# Initial_Schematic.net
KiCad netlist of a schematic drawn in EAGLE
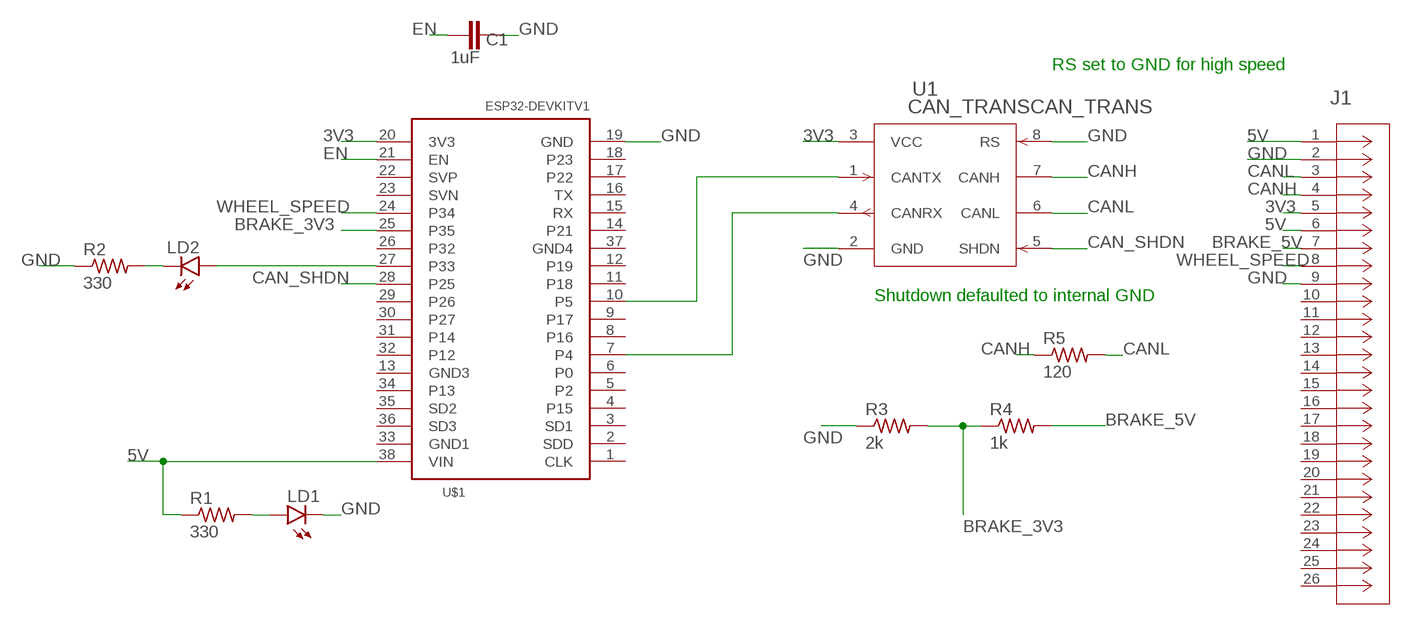
[diagram p0: schematic, sheet 1]

(export (version "E")
  (design (tool "Eeschema 10.0.6"))
  (components
    (comp (ref "C1")
      (value "1uF")
      (footprint "eagle-import:C1206")
      (libsource (lib "eagle-import") (part "CAPACITORC1206"))
    )
    (comp (ref "J1")
      (value "CONNECTOR")
      (footprint "eagle-import:CONN26_9-6437287-8_TEC")
      (fields
        (field (name "MANUFACTURER_PART_NUMBER") "9-6437287-8")
        (field (name "COPYRIGHT") "Copyright (C) 2022 Ultra Librarian. All rights reserved.")
      )
      (libsource (lib "eagle-import") (part "CONNECTOR"))
    )
    (comp (ref "LD1")
      (value "PL006-WCR21")
      (footprint "eagle-import:SOT23")
      (libsource (lib "eagle-import") (part "PL006-WCR21"))
    )
    (comp (ref "LD2")
      (value "PL006-WCR21")
      (footprint "eagle-import:SOT23")
      (libsource (lib "eagle-import") (part "PL006-WCR21"))
    )
    (comp (ref "R1")
      (value "330")
      (footprint "eagle-import:R1206")
      (libsource (lib "eagle-import") (part "RESISTORR1206"))
    )
    (comp (ref "R2")
      (value "330")
      (footprint "eagle-import:R1206")
      (libsource (lib "eagle-import") (part "RESISTORR1206"))
    )
    (comp (ref "R3")
      (value "2k")
      (footprint "eagle-import:R1206")
      (libsource (lib "eagle-import") (part "RESISTORR1206"))
    )
    (comp (ref "R4")
      (value "1k")
      (footprint "eagle-import:R1206")
      (libsource (lib "eagle-import") (part "RESISTORR1206"))
    )
    (comp (ref "R5")
      (value "120")
      (footprint "eagle-import:R1206")
      (libsource (lib "eagle-import") (part "RESISTORR1206"))
    )
    (comp (ref "U$1")
      (value "ESP32DEVKITV1")
      (footprint "eagle-import:ESP32-DEVKITV1")
      (libsource (lib "eagle-import") (part "ESP32DEVKITV1"))
    )
    (comp (ref "U1")
      (value "CAN_TRANSCAN_TRANS")
      (footprint "eagle-import:MAX3051ESA+")
      (fields
        (field (name "MANUFACTURER_PART_NUMBER") "MAX3051ESA+")
        (field (name "COPYRIGHT") "Copyright (C) 2022 Ultra Librarian. All rights reserved.")
      )
      (libsource (lib "eagle-import") (part "CAN_TRANSCAN_TRANS"))
    )
  )
  (nets
    (net (code "1") (name "/3V3") (class "Default")
      (node (ref "J1") (pin "5") (pinfunction "5_5") (pintype "passive"))
      (node (ref "U$1") (pin "20") (pinfunction "3V3_20") (pintype "bidirectional"))
      (node (ref "U1") (pin "3") (pinfunction "VCC_3") (pintype "power_in"))
    )
    (net (code "2") (name "/5V") (class "Default")
      (node (ref "J1") (pin "1") (pinfunction "1_1") (pintype "passive"))
      (node (ref "J1") (pin "6") (pinfunction "6_6") (pintype "passive"))
      (node (ref "R1") (pin "1") (pinfunction "1_1") (pintype "passive"))
      (node (ref "U$1") (pin "38") (pinfunction "VIN_38") (pintype "bidirectional"))
    )
    (net (code "3") (name "/BRAKE_3V3") (class "Default")
      (node (ref "R3") (pin "2") (pinfunction "2_2") (pintype "passive"))
      (node (ref "R4") (pin "1") (pinfunction "1_1") (pintype "passive"))
      (node (ref "U$1") (pin "25") (pinfunction "P35_25") (pintype "bidirectional"))
    )
    (net (code "4") (name "/BRAKE_5V") (class "Default")
      (node (ref "J1") (pin "7") (pinfunction "7_7") (pintype "passive"))
      (node (ref "R4") (pin "2") (pinfunction "2_2") (pintype "passive"))
    )
    (net (code "5") (name "/CANH") (class "Default")
      (node (ref "J1") (pin "4") (pinfunction "4_4") (pintype "passive"))
      (node (ref "R5") (pin "1") (pinfunction "1_1") (pintype "passive"))
      (node (ref "U1") (pin "7") (pinfunction "CANH_7") (pintype "passive"))
    )
    (net (code "6") (name "/CANL") (class "Default")
      (node (ref "J1") (pin "3") (pinfunction "3_3") (pintype "passive"))
      (node (ref "R5") (pin "2") (pinfunction "2_2") (pintype "passive"))
      (node (ref "U1") (pin "6") (pinfunction "CANL_6") (pintype "passive"))
    )
    (net (code "7") (name "/CAN_SHDN") (class "Default")
      (node (ref "U$1") (pin "28") (pinfunction "P25_28") (pintype "bidirectional"))
      (node (ref "U1") (pin "5") (pinfunction "SHDN_5") (pintype "input"))
    )
    (net (code "8") (name "/EN") (class "Default")
      (node (ref "C1") (pin "2") (pinfunction "2_2") (pintype "passive"))
      (node (ref "U$1") (pin "21") (pinfunction "EN_21") (pintype "bidirectional"))
    )
    (net (code "9") (name "/GND") (class "Default")
      (node (ref "C1") (pin "1") (pinfunction "1_1") (pintype "passive"))
      (node (ref "J1") (pin "2") (pinfunction "2_2") (pintype "passive"))
      (node (ref "J1") (pin "9") (pinfunction "9_9") (pintype "passive"))
      (node (ref "LD1") (pin "1") (pinfunction "C_1") (pintype "passive"))
      (node (ref "R2") (pin "1") (pinfunction "1_1") (pintype "passive"))
      (node (ref "R3") (pin "1") (pinfunction "1_1") (pintype "passive"))
      (node (ref "U$1") (pin "19") (pinfunction "GND_19") (pintype "bidirectional"))
      (node (ref "U1") (pin "2") (pinfunction "GND_2") (pintype "power_in"))
      (node (ref "U1") (pin "8") (pinfunction "RS_8") (pintype "input"))
    )
    (net (code "10") (name "/WHEEL_SPEED") (class "Default")
      (node (ref "J1") (pin "8") (pinfunction "8_8") (pintype "passive"))
      (node (ref "U$1") (pin "24") (pinfunction "P34_24") (pintype "bidirectional"))
    )
    (net (code "11") (name "Net-(LD1-A)") (class "Default")
      (node (ref "LD1") (pin "3") (pinfunction "A_3") (pintype "passive"))
      (node (ref "R1") (pin "2") (pinfunction "2_2") (pintype "passive"))
    )
    (net (code "12") (name "Net-(LD2-A)") (class "Default")
      (node (ref "LD2") (pin "3") (pinfunction "A_3") (pintype "passive"))
      (node (ref "U$1") (pin "27") (pinfunction "P33_27") (pintype "bidirectional"))
    )
    (net (code "13") (name "Net-(LD2-C)") (class "Default")
      (node (ref "LD2") (pin "1") (pinfunction "C_1") (pintype "passive"))
      (node (ref "R2") (pin "2") (pinfunction "2_2") (pintype "passive"))
    )
    (net (code "14") (name "Net-(U$1-P4)") (class "Default")
      (node (ref "U$1") (pin "7") (pinfunction "P4_7") (pintype "bidirectional"))
      (node (ref "U1") (pin "4") (pinfunction "CANRX_4") (pintype "output"))
    )
    (net (code "15") (name "Net-(U$1-P5)") (class "Default")
      (node (ref "U$1") (pin "10") (pinfunction "P5_10") (pintype "bidirectional"))
      (node (ref "U1") (pin "1") (pinfunction "CANTX_1") (pintype "input"))
    )
    (net (code "16") (name "unconnected-(J1-Pad10)") (class "Default")
      (node (ref "J1") (pin "10") (pinfunction "10_10") (pintype "passive"))
    )
    (net (code "17") (name "unconnected-(J1-Pad11)") (class "Default")
      (node (ref "J1") (pin "11") (pinfunction "11_11") (pintype "passive"))
    )
    (net (code "18") (name "unconnected-(J1-Pad12)") (class "Default")
      (node (ref "J1") (pin "12") (pinfunction "12_12") (pintype "passive"))
    )
    (net (code "19") (name "unconnected-(J1-Pad13)") (class "Default")
      (node (ref "J1") (pin "13") (pinfunction "13_13") (pintype "passive"))
    )
    (net (code "20") (name "unconnected-(J1-Pad14)") (class "Default")
      (node (ref "J1") (pin "14") (pinfunction "14_14") (pintype "passive"))
    )
    (net (code "21") (name "unconnected-(J1-Pad15)") (class "Default")
      (node (ref "J1") (pin "15") (pinfunction "15_15") (pintype "passive"))
    )
    (net (code "22") (name "unconnected-(J1-Pad16)") (class "Default")
      (node (ref "J1") (pin "16") (pinfunction "16_16") (pintype "passive"))
    )
    (net (code "23") (name "unconnected-(J1-Pad17)") (class "Default")
      (node (ref "J1") (pin "17") (pinfunction "17_17") (pintype "passive"))
    )
    (net (code "24") (name "unconnected-(J1-Pad18)") (class "Default")
      (node (ref "J1") (pin "18") (pinfunction "18_18") (pintype "passive"))
    )
    (net (code "25") (name "unconnected-(J1-Pad19)") (class "Default")
      (node (ref "J1") (pin "19") (pinfunction "19_19") (pintype "passive"))
    )
    (net (code "26") (name "unconnected-(J1-Pad20)") (class "Default")
      (node (ref "J1") (pin "20") (pinfunction "20_20") (pintype "passive"))
    )
    (net (code "27") (name "unconnected-(J1-Pad21)") (class "Default")
      (node (ref "J1") (pin "21") (pinfunction "21_21") (pintype "passive"))
    )
    (net (code "28") (name "unconnected-(J1-Pad22)") (class "Default")
      (node (ref "J1") (pin "22") (pinfunction "22_22") (pintype "passive"))
    )
    (net (code "29") (name "unconnected-(J1-Pad23)") (class "Default")
      (node (ref "J1") (pin "23") (pinfunction "23_23") (pintype "passive"))
    )
    (net (code "30") (name "unconnected-(J1-Pad24)") (class "Default")
      (node (ref "J1") (pin "24") (pinfunction "24_24") (pintype "passive"))
    )
    (net (code "31") (name "unconnected-(J1-Pad25)") (class "Default")
      (node (ref "J1") (pin "25") (pinfunction "25_25") (pintype "passive"))
    )
    (net (code "32") (name "unconnected-(J1-Pad26)") (class "Default")
      (node (ref "J1") (pin "26") (pinfunction "26_26") (pintype "passive"))
    )
    (net (code "33") (name "unconnected-(U$1-CLK-Pad1)") (class "Default")
      (node (ref "U$1") (pin "1") (pinfunction "CLK_1") (pintype "bidirectional"))
    )
    (net (code "34") (name "unconnected-(U$1-GND1-Pad33)") (class "Default")
      (node (ref "U$1") (pin "33") (pinfunction "GND1_33") (pintype "bidirectional"))
    )
    (net (code "35") (name "unconnected-(U$1-GND3-Pad13)") (class "Default")
      (node (ref "U$1") (pin "13") (pinfunction "GND3_13") (pintype "bidirectional"))
    )
    (net (code "36") (name "unconnected-(U$1-GND4-Pad37)") (class "Default")
      (node (ref "U$1") (pin "37") (pinfunction "GND4_37") (pintype "bidirectional"))
    )
    (net (code "37") (name "unconnected-(U$1-P0-Pad6)") (class "Default")
      (node (ref "U$1") (pin "6") (pinfunction "P0_6") (pintype "bidirectional"))
    )
    (net (code "38") (name "unconnected-(U$1-P2-Pad5)") (class "Default")
      (node (ref "U$1") (pin "5") (pinfunction "P2_5") (pintype "bidirectional"))
    )
    (net (code "39") (name "unconnected-(U$1-P12-Pad32)") (class "Default")
      (node (ref "U$1") (pin "32") (pinfunction "P12_32") (pintype "bidirectional"))
    )
    (net (code "40") (name "unconnected-(U$1-P13-Pad34)") (class "Default")
      (node (ref "U$1") (pin "34") (pinfunction "P13_34") (pintype "bidirectional"))
    )
    (net (code "41") (name "unconnected-(U$1-P14-Pad31)") (class "Default")
      (node (ref "U$1") (pin "31") (pinfunction "P14_31") (pintype "bidirectional"))
    )
    (net (code "42") (name "unconnected-(U$1-P15-Pad4)") (class "Default")
      (node (ref "U$1") (pin "4") (pinfunction "P15_4") (pintype "bidirectional"))
    )
    (net (code "43") (name "unconnected-(U$1-P16-Pad8)") (class "Default")
      (node (ref "U$1") (pin "8") (pinfunction "P16_8") (pintype "bidirectional"))
    )
    (net (code "44") (name "unconnected-(U$1-P17-Pad9)") (class "Default")
      (node (ref "U$1") (pin "9") (pinfunction "P17_9") (pintype "bidirectional"))
    )
    (net (code "45") (name "unconnected-(U$1-P18-Pad11)") (class "Default")
      (node (ref "U$1") (pin "11") (pinfunction "P18_11") (pintype "bidirectional"))
    )
    (net (code "46") (name "unconnected-(U$1-P19-Pad12)") (class "Default")
      (node (ref "U$1") (pin "12") (pinfunction "P19_12") (pintype "bidirectional"))
    )
    (net (code "47") (name "unconnected-(U$1-P21-Pad14)") (class "Default")
      (node (ref "U$1") (pin "14") (pinfunction "P21_14") (pintype "bidirectional"))
    )
    (net (code "48") (name "unconnected-(U$1-P22-Pad17)") (class "Default")
      (node (ref "U$1") (pin "17") (pinfunction "P22_17") (pintype "bidirectional"))
    )
    (net (code "49") (name "unconnected-(U$1-P23-Pad18)") (class "Default")
      (node (ref "U$1") (pin "18") (pinfunction "P23_18") (pintype "bidirectional"))
    )
    (net (code "50") (name "unconnected-(U$1-P26-Pad29)") (class "Default")
      (node (ref "U$1") (pin "29") (pinfunction "P26_29") (pintype "bidirectional"))
    )
    (net (code "51") (name "unconnected-(U$1-P27-Pad30)") (class "Default")
      (node (ref "U$1") (pin "30") (pinfunction "P27_30") (pintype "bidirectional"))
    )
    (net (code "52") (name "unconnected-(U$1-P32-Pad26)") (class "Default")
      (node (ref "U$1") (pin "26") (pinfunction "P32_26") (pintype "bidirectional"))
    )
    (net (code "53") (name "unconnected-(U$1-RX-Pad15)") (class "Default")
      (node (ref "U$1") (pin "15") (pinfunction "RX_15") (pintype "bidirectional"))
    )
    (net (code "54") (name "unconnected-(U$1-SD1-Pad3)") (class "Default")
      (node (ref "U$1") (pin "3") (pinfunction "SD1_3") (pintype "bidirectional"))
    )
    (net (code "55") (name "unconnected-(U$1-SD2-Pad35)") (class "Default")
      (node (ref "U$1") (pin "35") (pinfunction "SD2_35") (pintype "bidirectional"))
    )
    (net (code "56") (name "unconnected-(U$1-SD3-Pad36)") (class "Default")
      (node (ref "U$1") (pin "36") (pinfunction "SD3_36") (pintype "bidirectional"))
    )
    (net (code "57") (name "unconnected-(U$1-SDD-Pad2)") (class "Default")
      (node (ref "U$1") (pin "2") (pinfunction "SDD_2") (pintype "bidirectional"))
    )
    (net (code "58") (name "unconnected-(U$1-SVN-Pad23)") (class "Default")
      (node (ref "U$1") (pin "23") (pinfunction "SVN_23") (pintype "bidirectional"))
    )
    (net (code "59") (name "unconnected-(U$1-SVP-Pad22)") (class "Default")
      (node (ref "U$1") (pin "22") (pinfunction "SVP_22") (pintype "bidirectional"))
    )
    (net (code "60") (name "unconnected-(U$1-TX-Pad16)") (class "Default")
      (node (ref "U$1") (pin "16") (pinfunction "TX_16") (pintype "bidirectional"))
    )
  )
)
